# 1_-_Top.net
KiCad netlist of a schematic drawn in Altium Designer
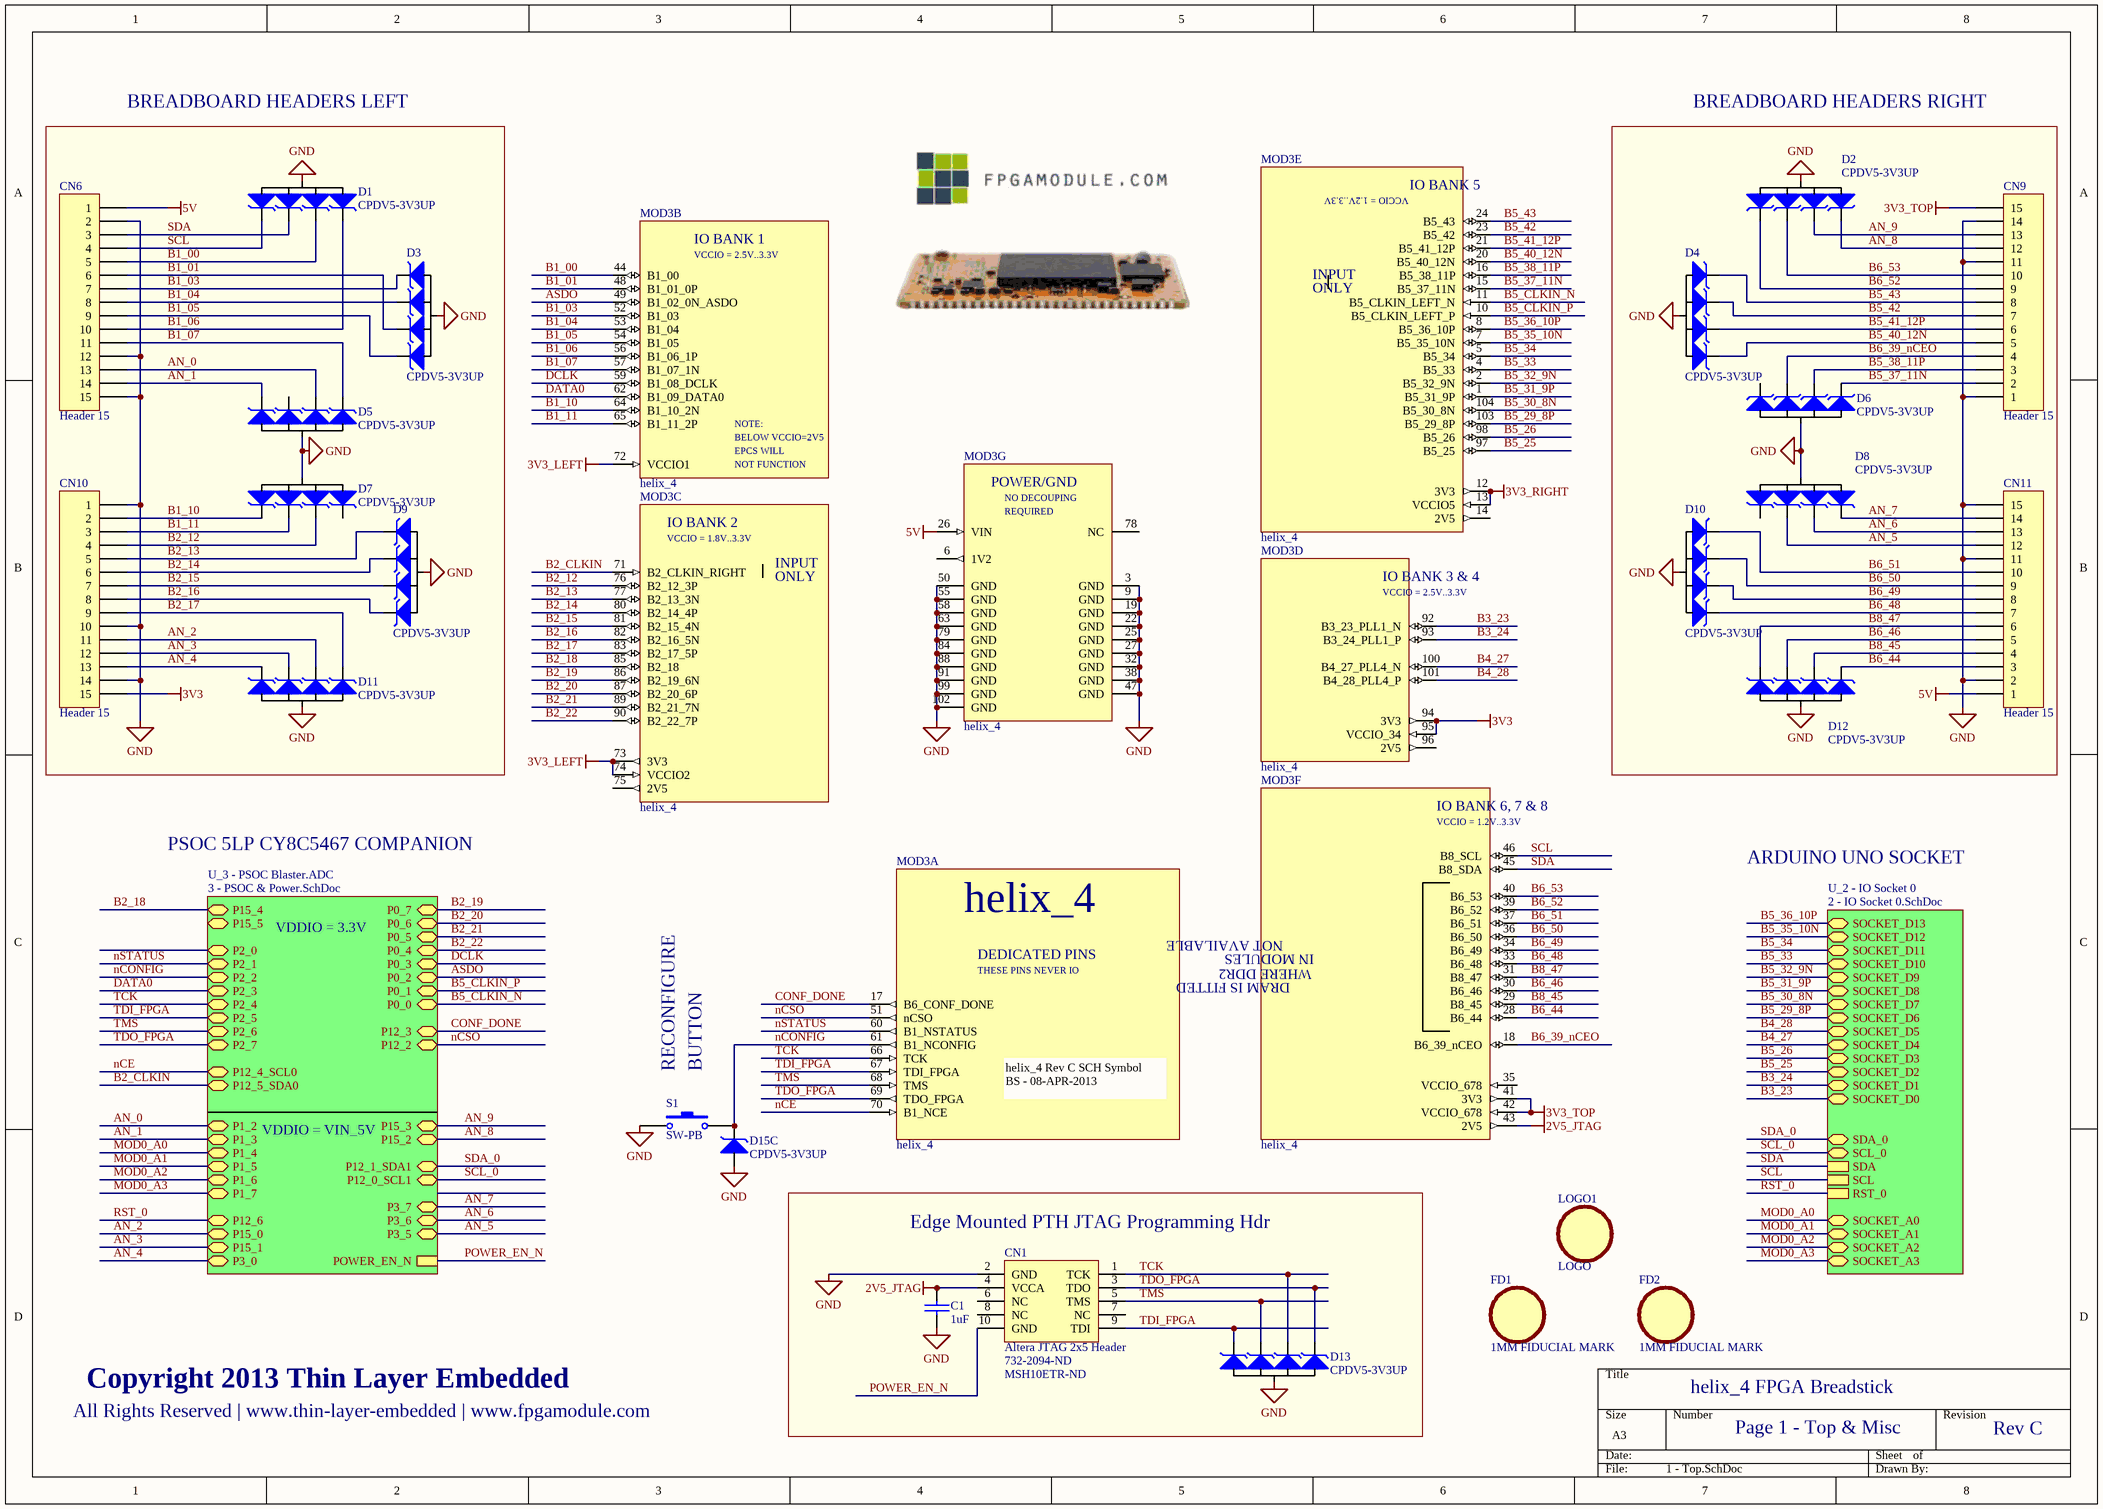
[diagram p0: 1 - Top.SchDoc]

(export (version "E")
  (design (tool "Eeschema 10.0.6"))
  (components
    (comp (ref "C1")
      (value "1uF")
      (footprint "0805")
      (description "Capacitor")
      (libsource (lib "*") (part "CAP"))
    )
    (comp (ref "CN1")
      (value "Altera JTAG 2x5 Header")
      (footprint "BOXHDR2X5_EDGE")
      (description "Header, 5-Pin, Dual row")
      (fields
        (field (name "MANUFACTURER") "Wurth Electronics Inc")
        (field (name "MANUFACTURER PART NUMBER") "61201021621")
        (field (name "SUPPLIER PART NUMBER 1") "732-2094-ND")
        (field (name "SUPPLIER PART NUMBER 2") "MSH10ETR-ND")
        (field (name "PUBLISHER") "Altium Limited")
      )
      (libsource (lib "master_library") (part "Altera JTAG 2x5 Header"))
    )
    (comp (ref "CN6")
      (value "Header 15")
      (footprint "HDR1X15")
      (description "Header, 15-Pin")
      (fields (field (name "PUBLISHER") "Altium Limited"))
      (libsource (lib "") (part "Header 15_1"))
    )
    (comp (ref "CN9")
      (value "Header 15")
      (footprint "HDR1X15")
      (description "Header, 15-Pin")
      (fields (field (name "PUBLISHER") "Altium Limited"))
      (libsource (lib "Miscellaneous Connectors") (part "Header 15"))
    )
    (comp (ref "CN10")
      (value "Header 15")
      (footprint "HDR1X15")
      (description "Header, 15-Pin")
      (fields (field (name "PUBLISHER") "Altium Limited"))
      (libsource (lib "") (part "Header 15_1"))
    )
    (comp (ref "CN11")
      (value "Header 15")
      (footprint "HDR1X15")
      (description "Header, 15-Pin")
      (fields (field (name "PUBLISHER") "Altium Limited"))
      (libsource (lib "Miscellaneous Connectors") (part "Header 15"))
    )
    (comp (ref "D1")
      (value "CPDV5-3V3UP")
      (footprint "SOT-353")
      (description "4CH ESD DIODE 3V3/3.5V")
      (libsource (lib "master_library") (part "4CH ESD DIODE"))
    )
    (comp (ref "D2")
      (value "CPDV5-3V3UP")
      (footprint "SOT-353")
      (description "4CH ESD DIODE 3V3/3.5V")
      (libsource (lib "master_library") (part "4CH ESD DIODE"))
    )
    (comp (ref "D3")
      (value "CPDV5-3V3UP")
      (footprint "SOT-353")
      (description "4CH ESD DIODE 3V3/3.5V")
      (libsource (lib "master_library") (part "4CH ESD DIODE"))
    )
    (comp (ref "D4")
      (value "CPDV5-3V3UP")
      (footprint "SOT-353")
      (description "4CH ESD DIODE 3V3/3.5V")
      (libsource (lib "master_library") (part "4CH ESD DIODE"))
    )
    (comp (ref "D5")
      (value "CPDV5-3V3UP")
      (footprint "SOT-353")
      (description "4CH ESD DIODE 3V3/3.5V")
      (libsource (lib "master_library") (part "4CH ESD DIODE"))
    )
    (comp (ref "D6")
      (value "CPDV5-3V3UP")
      (footprint "SOT-353")
      (description "4CH ESD DIODE 3V3/3.5V")
      (libsource (lib "master_library") (part "4CH ESD DIODE"))
    )
    (comp (ref "D7")
      (value "CPDV5-3V3UP")
      (footprint "SOT-353")
      (description "4CH ESD DIODE 3V3/3.5V")
      (libsource (lib "master_library") (part "4CH ESD DIODE"))
    )
    (comp (ref "D8")
      (value "CPDV5-3V3UP")
      (footprint "SOT-353")
      (description "4CH ESD DIODE 3V3/3.5V")
      (libsource (lib "master_library") (part "4CH ESD DIODE"))
    )
    (comp (ref "D9")
      (value "CPDV5-3V3UP")
      (footprint "SOT-353")
      (description "4CH ESD DIODE 3V3/3.5V")
      (libsource (lib "master_library") (part "4CH ESD DIODE"))
    )
    (comp (ref "D10")
      (value "CPDV5-3V3UP")
      (footprint "SOT-353")
      (description "4CH ESD DIODE 3V3/3.5V")
      (libsource (lib "master_library") (part "4CH ESD DIODE"))
    )
    (comp (ref "D11")
      (value "CPDV5-3V3UP")
      (footprint "SOT-353")
      (description "4CH ESD DIODE 3V3/3.5V")
      (libsource (lib "master_library") (part "4CH ESD DIODE"))
    )
    (comp (ref "D12")
      (value "CPDV5-3V3UP")
      (footprint "SOT-353")
      (description "4CH ESD DIODE 3V3/3.5V")
      (libsource (lib "master_library") (part "4CH ESD DIODE"))
    )
    (comp (ref "D13")
      (value "CPDV5-3V3UP")
      (footprint "SOT-353")
      (description "4CH ESD DIODE 3V3/3.5V")
      (libsource (lib "master_library") (part "4CH ESD DIODE"))
    )
    (comp (ref "D15")
      (value "CPDV5-3V3UP")
      (footprint "sot-353")
      (description "4CH ESD DIODE 3V3/3.5V")
      (libsource (lib "master_library") (part "4CH ESD DIODE (SPLIT)"))
    )
    (comp (ref "FD1") (value "1MM FIDUCIAL MARK") (footprint "FID_1MM") (libsource (lib "OB_1") (part "FID")))
    (comp (ref "FD2") (value "1MM FIDUCIAL MARK") (footprint "FID_1MM") (libsource (lib "OB_1") (part "FID")))
    (comp (ref "LOGO1") (value "LOGO") (footprint "LOGO_SMALL - SILK") (libsource (lib "OB_1") (part "FID")))
    (comp (ref "MOD3")
      (value "helix_4")
      (footprint "HELIX_4_LCC104_HOST")
      (libsource (lib "") (part "helix_4 Rev C Module_1"))
    )
    (comp (ref "S1")
      (value "SW-PB")
      (footprint "FSM4JSMA")
      (description "Switch")
      (fields (field (name "PUBLISHER") "Altium Limited"))
      (libsource (lib "Miscellaneous Devices") (part "SW-PB"))
    )
  )
  (nets
    (net (code "1") (name "/AN_0") (class "Default")
      (node (ref "CN6") (pin "13") (pinfunction "13_13") (pintype "passive"))
      (node (ref "D5") (pin "5") (pinfunction "K1_5") (pintype "passive"))
    )
    (net (code "2") (name "/AN_1") (class "Default")
      (node (ref "CN6") (pin "14") (pinfunction "14_14") (pintype "passive"))
      (node (ref "D5") (pin "3") (pinfunction "K1_3") (pintype "passive"))
    )
    (net (code "3") (name "/AN_2") (class "Default")
      (node (ref "CN10") (pin "11") (pinfunction "11_11") (pintype "passive"))
      (node (ref "D11") (pin "5") (pinfunction "K1_5") (pintype "passive"))
    )
    (net (code "4") (name "/AN_3") (class "Default")
      (node (ref "CN10") (pin "12") (pinfunction "12_12") (pintype "passive"))
      (node (ref "D11") (pin "1") (pinfunction "K2_1") (pintype "passive"))
    )
    (net (code "5") (name "/AN_4") (class "Default")
      (node (ref "CN10") (pin "13") (pinfunction "13_13") (pintype "passive"))
      (node (ref "D11") (pin "3") (pinfunction "K1_3") (pintype "passive"))
    )
    (net (code "6") (name "/AN_5") (class "Default")
      (node (ref "CN11") (pin "12") (pinfunction "12_12") (pintype "passive"))
      (node (ref "D8") (pin "5") (pinfunction "K1_5") (pintype "passive"))
    )
    (net (code "7") (name "/AN_6") (class "Default")
      (node (ref "CN11") (pin "13") (pinfunction "13_13") (pintype "passive"))
      (node (ref "D8") (pin "1") (pinfunction "K2_1") (pintype "passive"))
    )
    (net (code "8") (name "/AN_7") (class "Default")
      (node (ref "CN11") (pin "14") (pinfunction "14_14") (pintype "passive"))
      (node (ref "D8") (pin "3") (pinfunction "K1_3") (pintype "passive"))
    )
    (net (code "9") (name "/AN_8") (class "Default")
      (node (ref "CN9") (pin "12") (pinfunction "12_12") (pintype "passive"))
      (node (ref "D2") (pin "4") (pinfunction "K2_4") (pintype "passive"))
    )
    (net (code "10") (name "/AN_9") (class "Default")
      (node (ref "CN9") (pin "13") (pinfunction "13_13") (pintype "passive"))
      (node (ref "D2") (pin "5") (pinfunction "K1_5") (pintype "passive"))
    )
    (net (code "11") (name "/ASDO") (class "Default")
      (node (ref "MOD3") (pin "49") (pinfunction "B1_02_0N_ASDO_49") (pintype "bidirectional"))
    )
    (net (code "12") (name "/B1_00") (class "Default")
      (node (ref "CN6") (pin "5") (pinfunction "5_5") (pintype "passive"))
      (node (ref "D1") (pin "1") (pinfunction "K2_1") (pintype "passive"))
      (node (ref "MOD3") (pin "44") (pinfunction "B1_00_44") (pintype "bidirectional"))
    )
    (net (code "13") (name "/B1_01") (class "Default")
      (node (ref "CN6") (pin "6") (pinfunction "6_6") (pintype "passive"))
      (node (ref "D3") (pin "5") (pinfunction "K1_5") (pintype "passive"))
      (node (ref "MOD3") (pin "48") (pinfunction "B1_01_0P_48") (pintype "bidirectional"))
    )
    (net (code "14") (name "/B1_03") (class "Default")
      (node (ref "CN6") (pin "7") (pinfunction "7_7") (pintype "passive"))
      (node (ref "D3") (pin "3") (pinfunction "K1_3") (pintype "passive"))
      (node (ref "MOD3") (pin "52") (pinfunction "B1_03_52") (pintype "bidirectional"))
    )
    (net (code "15") (name "/B1_04") (class "Default")
      (node (ref "CN6") (pin "8") (pinfunction "8_8") (pintype "passive"))
      (node (ref "D3") (pin "1") (pinfunction "K2_1") (pintype "passive"))
      (node (ref "MOD3") (pin "53") (pinfunction "B1_04_53") (pintype "bidirectional"))
    )
    (net (code "16") (name "/B1_05") (class "Default")
      (node (ref "CN6") (pin "9") (pinfunction "9_9") (pintype "passive"))
      (node (ref "D3") (pin "4") (pinfunction "K2_4") (pintype "passive"))
      (node (ref "MOD3") (pin "54") (pinfunction "B1_05_54") (pintype "bidirectional"))
    )
    (net (code "17") (name "/B1_06") (class "Default")
      (node (ref "CN6") (pin "10") (pinfunction "10_10") (pintype "passive"))
      (node (ref "D1") (pin "3") (pinfunction "K1_3") (pintype "passive"))
      (node (ref "MOD3") (pin "56") (pinfunction "B1_06_1P_56") (pintype "bidirectional"))
    )
    (net (code "18") (name "/B1_07") (class "Default")
      (node (ref "CN6") (pin "11") (pinfunction "11_11") (pintype "passive"))
      (node (ref "D5") (pin "4") (pinfunction "K2_4") (pintype "passive"))
      (node (ref "MOD3") (pin "57") (pinfunction "B1_07_1N_57") (pintype "bidirectional"))
    )
    (net (code "19") (name "/B1_10") (class "Default")
      (node (ref "CN10") (pin "2") (pinfunction "2_2") (pintype "passive"))
      (node (ref "D7") (pin "4") (pinfunction "K2_4") (pintype "passive"))
      (node (ref "MOD3") (pin "64") (pinfunction "B1_10_2N_64") (pintype "bidirectional"))
    )
    (net (code "20") (name "/B1_11") (class "Default")
      (node (ref "CN10") (pin "3") (pinfunction "3_3") (pintype "passive"))
      (node (ref "D7") (pin "5") (pinfunction "K1_5") (pintype "passive"))
      (node (ref "MOD3") (pin "65") (pinfunction "B1_11_2P_65") (pintype "bidirectional"))
    )
    (net (code "21") (name "/B2_12") (class "Default")
      (node (ref "CN10") (pin "4") (pinfunction "4_4") (pintype "passive"))
      (node (ref "D7") (pin "1") (pinfunction "K2_1") (pintype "passive"))
      (node (ref "MOD3") (pin "76") (pinfunction "B2_12_3P_76") (pintype "bidirectional"))
    )
    (net (code "22") (name "/B2_13") (class "Default")
      (node (ref "CN10") (pin "5") (pinfunction "5_5") (pintype "passive"))
      (node (ref "D9") (pin "4") (pinfunction "K2_4") (pintype "passive"))
      (node (ref "MOD3") (pin "77") (pinfunction "B2_13_3N_77") (pintype "bidirectional"))
    )
    (net (code "23") (name "/B2_14") (class "Default")
      (node (ref "CN10") (pin "6") (pinfunction "6_6") (pintype "passive"))
      (node (ref "D9") (pin "5") (pinfunction "K1_5") (pintype "passive"))
      (node (ref "MOD3") (pin "80") (pinfunction "B2_14_4P_80") (pintype "bidirectional"))
    )
    (net (code "24") (name "/B2_15") (class "Default")
      (node (ref "CN10") (pin "7") (pinfunction "7_7") (pintype "passive"))
      (node (ref "D9") (pin "1") (pinfunction "K2_1") (pintype "passive"))
      (node (ref "MOD3") (pin "81") (pinfunction "B2_15_4N_81") (pintype "bidirectional"))
    )
    (net (code "25") (name "/B2_16") (class "Default")
      (node (ref "CN10") (pin "8") (pinfunction "8_8") (pintype "passive"))
      (node (ref "D9") (pin "3") (pinfunction "K1_3") (pintype "passive"))
      (node (ref "MOD3") (pin "82") (pinfunction "B2_16_5N_82") (pintype "bidirectional"))
    )
    (net (code "26") (name "/B2_17") (class "Default")
      (node (ref "CN10") (pin "9") (pinfunction "9_9") (pintype "passive"))
      (node (ref "D11") (pin "4") (pinfunction "K2_4") (pintype "passive"))
      (node (ref "MOD3") (pin "83") (pinfunction "B2_17_5P_83") (pintype "bidirectional"))
    )
    (net (code "27") (name "/B2_18") (class "Default")
      (node (ref "MOD3") (pin "85") (pinfunction "B2_18_85") (pintype "bidirectional"))
    )
    (net (code "28") (name "/B2_19") (class "Default")
      (node (ref "MOD3") (pin "86") (pinfunction "B2_19_6N_86") (pintype "bidirectional"))
    )
    (net (code "29") (name "/B2_20") (class "Default")
      (node (ref "MOD3") (pin "87") (pinfunction "B2_20_6P_87") (pintype "bidirectional"))
    )
    (net (code "30") (name "/B2_21") (class "Default")
      (node (ref "MOD3") (pin "89") (pinfunction "B2_21_7N_89") (pintype "bidirectional"))
    )
    (net (code "31") (name "/B2_22") (class "Default")
      (node (ref "MOD3") (pin "90") (pinfunction "B2_22_7P_90") (pintype "bidirectional"))
    )
    (net (code "32") (name "/B2_CLKIN") (class "Default")
      (node (ref "MOD3") (pin "71") (pinfunction "B2_CLKIN_RIGHT_71") (pintype "input"))
    )
    (net (code "33") (name "/B3_23") (class "Default")
      (node (ref "MOD3") (pin "92") (pinfunction "B3_23_PLL1_N_92") (pintype "bidirectional"))
    )
    (net (code "34") (name "/B3_24") (class "Default")
      (node (ref "MOD3") (pin "93") (pinfunction "B3_24_PLL1_P_93") (pintype "bidirectional"))
    )
    (net (code "35") (name "/B4_27") (class "Default")
      (node (ref "MOD3") (pin "100") (pinfunction "B4_27_PLL4_N_100") (pintype "bidirectional"))
    )
    (net (code "36") (name "/B4_28") (class "Default")
      (node (ref "MOD3") (pin "101") (pinfunction "B4_28_PLL4_P_101") (pintype "bidirectional"))
    )
    (net (code "37") (name "/B5_25") (class "Default")
      (node (ref "MOD3") (pin "97") (pinfunction "B5_25_97") (pintype "bidirectional"))
    )
    (net (code "38") (name "/B5_26") (class "Default")
      (node (ref "MOD3") (pin "98") (pinfunction "B5_26_98") (pintype "bidirectional"))
    )
    (net (code "39") (name "/B5_29_8P") (class "Default")
      (node (ref "MOD3") (pin "103") (pinfunction "B5_29_8P_103") (pintype "bidirectional"))
    )
    (net (code "40") (name "/B5_30_8N") (class "Default")
      (node (ref "MOD3") (pin "104") (pinfunction "B5_30_8N_104") (pintype "bidirectional"))
    )
    (net (code "41") (name "/B5_31_9P") (class "Default")
      (node (ref "MOD3") (pin "1") (pinfunction "B5_31_9P_1") (pintype "bidirectional"))
    )
    (net (code "42") (name "/B5_32_9N") (class "Default")
      (node (ref "MOD3") (pin "2") (pinfunction "B5_32_9N_2") (pintype "bidirectional"))
    )
    (net (code "43") (name "/B5_33") (class "Default")
      (node (ref "MOD3") (pin "4") (pinfunction "B5_33_4") (pintype "bidirectional"))
    )
    (net (code "44") (name "/B5_34") (class "Default")
      (node (ref "MOD3") (pin "5") (pinfunction "B5_34_5") (pintype "bidirectional"))
    )
    (net (code "45") (name "/B5_35_10N") (class "Default")
      (node (ref "MOD3") (pin "7") (pinfunction "B5_35_10N_7") (pintype "bidirectional"))
    )
    (net (code "46") (name "/B5_36_10P") (class "Default")
      (node (ref "MOD3") (pin "8") (pinfunction "B5_36_10P_8") (pintype "bidirectional"))
    )
    (net (code "47") (name "/B5_37_11N") (class "Default")
      (node (ref "CN9") (pin "2") (pinfunction "2_2") (pintype "passive"))
      (node (ref "D6") (pin "3") (pinfunction "K1_3") (pintype "passive"))
      (node (ref "MOD3") (pin "15") (pinfunction "B5_37_11N_15") (pintype "bidirectional"))
    )
    (net (code "48") (name "/B5_38_11P") (class "Default")
      (node (ref "CN9") (pin "3") (pinfunction "3_3") (pintype "passive"))
      (node (ref "D6") (pin "1") (pinfunction "K2_1") (pintype "passive"))
      (node (ref "MOD3") (pin "16") (pinfunction "B5_38_11P_16") (pintype "bidirectional"))
    )
    (net (code "49") (name "/B5_40_12N") (class "Default")
      (node (ref "CN9") (pin "5") (pinfunction "5_5") (pintype "passive"))
      (node (ref "D4") (pin "3") (pinfunction "K1_3") (pintype "passive"))
      (node (ref "MOD3") (pin "20") (pinfunction "B5_40_12N_20") (pintype "bidirectional"))
    )
    (net (code "50") (name "/B5_41_12P") (class "Default")
      (node (ref "CN9") (pin "6") (pinfunction "6_6") (pintype "passive"))
      (node (ref "D4") (pin "1") (pinfunction "K2_1") (pintype "passive"))
      (node (ref "MOD3") (pin "21") (pinfunction "B5_41_12P_21") (pintype "bidirectional"))
    )
    (net (code "51") (name "/B5_42") (class "Default")
      (node (ref "CN9") (pin "7") (pinfunction "7_7") (pintype "passive"))
      (node (ref "D4") (pin "5") (pinfunction "K1_5") (pintype "passive"))
      (node (ref "MOD3") (pin "23") (pinfunction "B5_42_23") (pintype "bidirectional"))
    )
    (net (code "52") (name "/B5_43") (class "Default")
      (node (ref "CN9") (pin "8") (pinfunction "8_8") (pintype "passive"))
      (node (ref "D4") (pin "4") (pinfunction "K2_4") (pintype "passive"))
      (node (ref "MOD3") (pin "24") (pinfunction "B5_43_24") (pintype "bidirectional"))
    )
    (net (code "53") (name "/B5_CLKIN_N") (class "Default")
      (node (ref "MOD3") (pin "11") (pinfunction "B5_CLKIN_LEFT_N_11") (pintype "input"))
    )
    (net (code "54") (name "/B5_CLKIN_P") (class "Default")
      (node (ref "MOD3") (pin "10") (pinfunction "B5_CLKIN_LEFT_P_10") (pintype "input"))
    )
    (net (code "55") (name "/B6_39_nCEO") (class "Default")
      (node (ref "CN9") (pin "4") (pinfunction "4_4") (pintype "passive"))
      (node (ref "D6") (pin "5") (pinfunction "K1_5") (pintype "passive"))
      (node (ref "MOD3") (pin "18") (pinfunction "B6_39_nCEO_18") (pintype "bidirectional"))
    )
    (net (code "56") (name "/B6_44") (class "Default")
      (node (ref "CN11") (pin "3") (pinfunction "3_3") (pintype "passive"))
      (node (ref "D12") (pin "4") (pinfunction "K2_4") (pintype "passive"))
      (node (ref "MOD3") (pin "28") (pinfunction "B6_44_28") (pintype "bidirectional"))
    )
    (net (code "57") (name "/B6_46") (class "Default")
      (node (ref "CN11") (pin "5") (pinfunction "5_5") (pintype "passive"))
      (node (ref "D12") (pin "1") (pinfunction "K2_1") (pintype "passive"))
      (node (ref "MOD3") (pin "30") (pinfunction "B6_46_30") (pintype "bidirectional"))
    )
    (net (code "58") (name "/B6_48") (class "Default")
      (node (ref "CN11") (pin "7") (pinfunction "7_7") (pintype "passive"))
      (node (ref "D10") (pin "4") (pinfunction "K2_4") (pintype "passive"))
      (node (ref "MOD3") (pin "33") (pinfunction "B6_48_33") (pintype "bidirectional"))
    )
    (net (code "59") (name "/B6_49") (class "Default")
      (node (ref "CN11") (pin "8") (pinfunction "8_8") (pintype "passive"))
      (node (ref "D10") (pin "5") (pinfunction "K1_5") (pintype "passive"))
      (node (ref "MOD3") (pin "34") (pinfunction "B6_49_34") (pintype "bidirectional"))
    )
    (net (code "60") (name "/B6_50") (class "Default")
      (node (ref "CN11") (pin "9") (pinfunction "9_9") (pintype "passive"))
      (node (ref "D10") (pin "1") (pinfunction "K2_1") (pintype "passive"))
      (node (ref "MOD3") (pin "36") (pinfunction "B6_50_36") (pintype "bidirectional"))
    )
    (net (code "61") (name "/B6_51") (class "Default")
      (node (ref "CN11") (pin "10") (pinfunction "10_10") (pintype "passive"))
      (node (ref "D10") (pin "3") (pinfunction "K1_3") (pintype "passive"))
      (node (ref "MOD3") (pin "37") (pinfunction "B6_51_37") (pintype "bidirectional"))
    )
    (net (code "62") (name "/B6_52") (class "Default")
      (node (ref "CN9") (pin "9") (pinfunction "9_9") (pintype "passive"))
      (node (ref "D2") (pin "3") (pinfunction "K1_3") (pintype "passive"))
      (node (ref "MOD3") (pin "39") (pinfunction "B6_52_39") (pintype "bidirectional"))
    )
    (net (code "63") (name "/B6_53") (class "Default")
      (node (ref "CN9") (pin "10") (pinfunction "10_10") (pintype "passive"))
      (node (ref "D2") (pin "1") (pinfunction "K2_1") (pintype "passive"))
      (node (ref "MOD3") (pin "40") (pinfunction "B6_53_40") (pintype "bidirectional"))
    )
    (net (code "64") (name "/B8_45") (class "Default")
      (node (ref "CN11") (pin "4") (pinfunction "4_4") (pintype "passive"))
      (node (ref "D12") (pin "5") (pinfunction "K1_5") (pintype "passive"))
      (node (ref "MOD3") (pin "29") (pinfunction "B8_45_29") (pintype "bidirectional"))
    )
    (net (code "65") (name "/B8_47") (class "Default")
      (node (ref "CN11") (pin "6") (pinfunction "6_6") (pintype "passive"))
      (node (ref "D12") (pin "3") (pinfunction "K1_3") (pintype "passive"))
      (node (ref "MOD3") (pin "31") (pinfunction "B8_47_31") (pintype "bidirectional"))
    )
    (net (code "66") (name "/CONF_DONE") (class "Default")
      (node (ref "MOD3") (pin "17") (pinfunction "B6_CONF_DONE_17") (pintype "output"))
    )
    (net (code "67") (name "/DATA0") (class "Default")
      (node (ref "MOD3") (pin "62") (pinfunction "B1_09_DATA0_62") (pintype "bidirectional"))
    )
    (net (code "68") (name "/DCLK") (class "Default")
      (node (ref "MOD3") (pin "59") (pinfunction "B1_08_DCLK_59") (pintype "bidirectional"))
    )
    (net (code "75") (name "/POWER_EN_N") (class "Default")
      (node (ref "CN1") (pin "10") (pinfunction "GND_10") (pintype "passive"))
    )
    (net (code "77") (name "/SCL") (class "Default")
      (node (ref "CN6") (pin "4") (pinfunction "4_4") (pintype "passive"))
      (node (ref "D1") (pin "4") (pinfunction "K2_4") (pintype "passive"))
      (node (ref "MOD3") (pin "46") (pinfunction "B8_SCL_46") (pintype "bidirectional"))
    )
    (net (code "79") (name "/SDA") (class "Default")
      (node (ref "CN6") (pin "3") (pinfunction "3_3") (pintype "passive"))
      (node (ref "D1") (pin "5") (pinfunction "K1_5") (pintype "passive"))
      (node (ref "MOD3") (pin "45") (pinfunction "B8_SDA_45") (pintype "bidirectional"))
    )
    (net (code "81") (name "/TCK") (class "Default")
      (node (ref "CN1") (pin "1") (pinfunction "TCK_1") (pintype "passive"))
      (node (ref "D13") (pin "5") (pinfunction "K1_5") (pintype "passive"))
      (node (ref "MOD3") (pin "66") (pinfunction "TCK_66") (pintype "input"))
    )
    (net (code "82") (name "/TDI_FPGA") (class "Default")
      (node (ref "CN1") (pin "9") (pinfunction "TDI_9") (pintype "passive"))
      (node (ref "D13") (pin "3") (pinfunction "K1_3") (pintype "passive"))
      (node (ref "MOD3") (pin "67") (pinfunction "TDI_FPGA_67") (pintype "input"))
    )
    (net (code "83") (name "/TDO_FPGA") (class "Default")
      (node (ref "CN1") (pin "3") (pinfunction "TDO_3") (pintype "passive"))
      (node (ref "D13") (pin "4") (pinfunction "K2_4") (pintype "passive"))
      (node (ref "MOD3") (pin "69") (pinfunction "TDO_FPGA_69") (pintype "output"))
    )
    (net (code "84") (name "/TMS") (class "Default")
      (node (ref "CN1") (pin "5") (pinfunction "TMS_5") (pintype "passive"))
      (node (ref "D13") (pin "1") (pinfunction "K2_1") (pintype "passive"))
      (node (ref "MOD3") (pin "68") (pinfunction "TMS_68") (pintype "input"))
    )
    (net (code "85") (name "/nCE") (class "Default")
      (node (ref "MOD3") (pin "70") (pinfunction "B1_NCE_70") (pintype "input"))
    )
    (net (code "86") (name "/nCONFIG") (class "Default")
      (node (ref "D15") (pin "5") (pinfunction "K3_5") (pintype "passive"))
      (node (ref "MOD3") (pin "61") (pinfunction "B1_NCONFIG_61") (pintype "output"))
      (node (ref "S1") (pin "2") (pinfunction "2_2") (pintype "passive"))
    )
    (net (code "87") (name "/nCSO") (class "Default")
      (node (ref "MOD3") (pin "51") (pinfunction "nCSO_51") (pintype "output"))
    )
    (net (code "88") (name "/nSTATUS") (class "Default")
      (node (ref "MOD3") (pin "60") (pinfunction "B1_NSTATUS_60") (pintype "output"))
    )
    (net (code "89") (name "2V5_JTAG") (class "Default")
      (node (ref "C1") (pin "2") (pinfunction "2_2") (pintype "passive"))
      (node (ref "CN1") (pin "4") (pinfunction "VCCA_4") (pintype "passive"))
      (node (ref "MOD3") (pin "43") (pinfunction "2V5_43") (pintype "output"))
    )
    (net (code "90") (name "3V3") (class "Default")
      (node (ref "CN10") (pin "15") (pinfunction "15_15") (pintype "passive"))
      (node (ref "MOD3") (pin "94") (pinfunction "3V3_94") (pintype "output"))
      (node (ref "MOD3") (pin "95") (pinfunction "VCCIO_34_95") (pintype "input"))
    )
    (net (code "91") (name "3V3_LEFT") (class "Default")
      (node (ref "MOD3") (pin "72") (pinfunction "VCCIO1_72") (pintype "input"))
      (node (ref "MOD3") (pin "73") (pinfunction "3V3_73") (pintype "output"))
      (node (ref "MOD3") (pin "74") (pinfunction "VCCIO2_74") (pintype "input"))
    )
    (net (code "92") (name "3V3_RIGHT") (class "Default")
      (node (ref "MOD3") (pin "12") (pinfunction "3V3_12") (pintype "output"))
      (node (ref "MOD3") (pin "13") (pinfunction "VCCIO5_13") (pintype "input"))
    )
    (net (code "93") (name "3V3_TOP") (class "Default")
      (node (ref "CN9") (pin "15") (pinfunction "15_15") (pintype "passive"))
      (node (ref "MOD3") (pin "41") (pinfunction "3V3_41") (pintype "output"))
      (node (ref "MOD3") (pin "42") (pinfunction "VCCIO_678_42") (pintype "input"))
    )
    (net (code "94") (name "5V") (class "Default")
      (node (ref "CN11") (pin "1") (pinfunction "1_1") (pintype "passive"))
      (node (ref "CN6") (pin "1") (pinfunction "1_1") (pintype "passive"))
      (node (ref "MOD3") (pin "26") (pinfunction "VIN_26") (pintype "input"))
    )
    (net (code "95") (name "GND") (class "Default")
      (node (ref "C1") (pin "1") (pinfunction "1_1") (pintype "passive"))
      (node (ref "CN1") (pin "2") (pinfunction "GND_2") (pintype "passive"))
      (node (ref "CN10") (pin "1") (pinfunction "1_1") (pintype "passive"))
      (node (ref "CN10") (pin "10") (pinfunction "10_10") (pintype "passive"))
      (node (ref "CN10") (pin "14") (pinfunction "14_14") (pintype "passive"))
      (node (ref "CN11") (pin "11") (pinfunction "11_11") (pintype "passive"))
      (node (ref "CN11") (pin "15") (pinfunction "15_15") (pintype "passive"))
      (node (ref "CN11") (pin "2") (pinfunction "2_2") (pintype "passive"))
      (node (ref "CN6") (pin "12") (pinfunction "12_12") (pintype "passive"))
      (node (ref "CN6") (pin "15") (pinfunction "15_15") (pintype "passive"))
      (node (ref "CN6") (pin "2") (pinfunction "2_2") (pintype "passive"))
      (node (ref "CN9") (pin "1") (pinfunction "1_1") (pintype "passive"))
      (node (ref "CN9") (pin "11") (pinfunction "11_11") (pintype "passive"))
      (node (ref "CN9") (pin "14") (pinfunction "14_14") (pintype "passive"))
      (node (ref "D1") (pin "2") (pinfunction "A_2") (pintype "passive"))
      (node (ref "D10") (pin "2") (pinfunction "A_2") (pintype "passive"))
      (node (ref "D11") (pin "2") (pinfunction "A_2") (pintype "passive"))
      (node (ref "D12") (pin "2") (pinfunction "A_2") (pintype "passive"))
      (node (ref "D13") (pin "2") (pinfunction "A_2") (pintype "passive"))
      (node (ref "D15") (pin "2") (pinfunction "A_2") (pintype "passive"))
      (node (ref "D2") (pin "2") (pinfunction "A_2") (pintype "passive"))
      (node (ref "D3") (pin "2") (pinfunction "A_2") (pintype "passive"))
      (node (ref "D4") (pin "2") (pinfunction "A_2") (pintype "passive"))
      (node (ref "D5") (pin "2") (pinfunction "A_2") (pintype "passive"))
      (node (ref "D6") (pin "2") (pinfunction "A_2") (pintype "passive"))
      (node (ref "D7") (pin "2") (pinfunction "A_2") (pintype "passive"))
      (node (ref "D8") (pin "2") (pinfunction "A_2") (pintype "passive"))
      (node (ref "D9") (pin "2") (pinfunction "A_2") (pintype "passive"))
      (node (ref "MOD3") (pin "102") (pinfunction "GND_102") (pintype "passive"))
      (node (ref "MOD3") (pin "19") (pinfunction "GND_19") (pintype "passive"))
      (node (ref "MOD3") (pin "22") (pinfunction "GND_22") (pintype "passive"))
      (node (ref "MOD3") (pin "25") (pinfunction "GND_25") (pintype "passive"))
      (node (ref "MOD3") (pin "27") (pinfunction "GND_27") (pintype "passive"))
      (node (ref "MOD3") (pin "3") (pinfunction "GND_3") (pintype "passive"))
      (node (ref "MOD3") (pin "32") (pinfunction "GND_32") (pintype "passive"))
      (node (ref "MOD3") (pin "38") (pinfunction "GND_38") (pintype "passive"))
      (node (ref "MOD3") (pin "47") (pinfunction "GND_47") (pintype "passive"))
      (node (ref "MOD3") (pin "50") (pinfunction "GND_50") (pintype "passive"))
      (node (ref "MOD3") (pin "55") (pinfunction "GND_55") (pintype "passive"))
      (node (ref "MOD3") (pin "58") (pinfunction "GND_58") (pintype "passive"))
      (node (ref "MOD3") (pin "63") (pinfunction "GND_63") (pintype "passive"))
      (node (ref "MOD3") (pin "79") (pinfunction "GND_79") (pintype "passive"))
      (node (ref "MOD3") (pin "84") (pinfunction "GND_84") (pintype "passive"))
      (node (ref "MOD3") (pin "88") (pinfunction "GND_88") (pintype "passive"))
      (node (ref "MOD3") (pin "9") (pinfunction "GND_9") (pintype "passive"))
      (node (ref "MOD3") (pin "91") (pinfunction "GND_91") (pintype "passive"))
      (node (ref "MOD3") (pin "99") (pinfunction "GND_99") (pintype "passive"))
      (node (ref "S1") (pin "1") (pinfunction "1_1") (pintype "passive"))
    )
    (net (code "96") (name "unconnected-(CN1-NC-Pad6)") (class "Default")
      (node (ref "CN1") (pin "6") (pinfunction "NC_6") (pintype "passive"))
    )
    (net (code "97") (name "unconnected-(CN1-NC-Pad7)") (class "Default")
      (node (ref "CN1") (pin "7") (pinfunction "NC_7") (pintype "passive"))
    )
    (net (code "98") (name "unconnected-(CN1-NC-Pad8)") (class "Default")
      (node (ref "CN1") (pin "8") (pinfunction "NC_8") (pintype "passive"))
    )
    (net (code "99") (name "unconnected-(D5-K2-Pad1)") (class "Default")
      (node (ref "D5") (pin "1") (pinfunction "K2_1") (pintype "passive"))
    )
    (net (code "100") (name "unconnected-(D6-K2-Pad4)") (class "Default")
      (node (ref "D6") (pin "4") (pinfunction "K2_4") (pintype "passive"))
    )
    (net (code "101") (name "unconnected-(D7-K1-Pad3)") (class "Default")
      (node (ref "D7") (pin "3") (pinfunction "K1_3") (pintype "passive"))
    )
    (net (code "102") (name "unconnected-(D8-K2-Pad4)") (class "Default")
      (node (ref "D8") (pin "4") (pinfunction "K2_4") (pintype "passive"))
    )
    (net (code "103") (name "unconnected-(FD1-FID-Pad1)") (class "Default")
      (node (ref "FD1") (pin "1") (pinfunction "FID_1") (pintype "passive"))
    )
    (net (code "104") (name "unconnected-(FD2-FID-Pad1)") (class "Default")
      (node (ref "FD2") (pin "1") (pinfunction "FID_1") (pintype "passive"))
    )
    (net (code "105") (name "unconnected-(LOGO1-FID-Pad1)") (class "Default")
      (node (ref "LOGO1") (pin "1") (pinfunction "FID_1") (pintype "passive"))
    )
    (net (code "106") (name "unconnected-(MOD3C-2V5-Pad75)") (class "Default")
      (node (ref "MOD3") (pin "75") (pinfunction "2V5_75") (pintype "output"))
    )
    (net (code "107") (name "unconnected-(MOD3D-2V5-Pad96)") (class "Default")
      (node (ref "MOD3") (pin "96") (pinfunction "2V5_96") (pintype "output"))
    )
    (net (code "108") (name "unconnected-(MOD3E-2V5-Pad14)") (class "Default")
      (node (ref "MOD3") (pin "14") (pinfunction "2V5_14") (pintype "output"))
    )
    (net (code "109") (name "unconnected-(MOD3F-VCCIO_678-Pad35)") (class "Default")
      (node (ref "MOD3") (pin "35") (pinfunction "VCCIO_678_35") (pintype "input"))
    )
    (net (code "110") (name "unconnected-(MOD3G-1V2-Pad6)") (class "Default")
      (node (ref "MOD3") (pin "6") (pinfunction "1V2_6") (pintype "output"))
    )
    (net (code "111") (name "unconnected-(MOD3G-NC-Pad78)") (class "Default")
      (node (ref "MOD3") (pin "78") (pinfunction "NC_78") (pintype "passive"))
    )
  )
)
